# Sheet1.net
KiCad netlist of a schematic drawn in Altium Designer
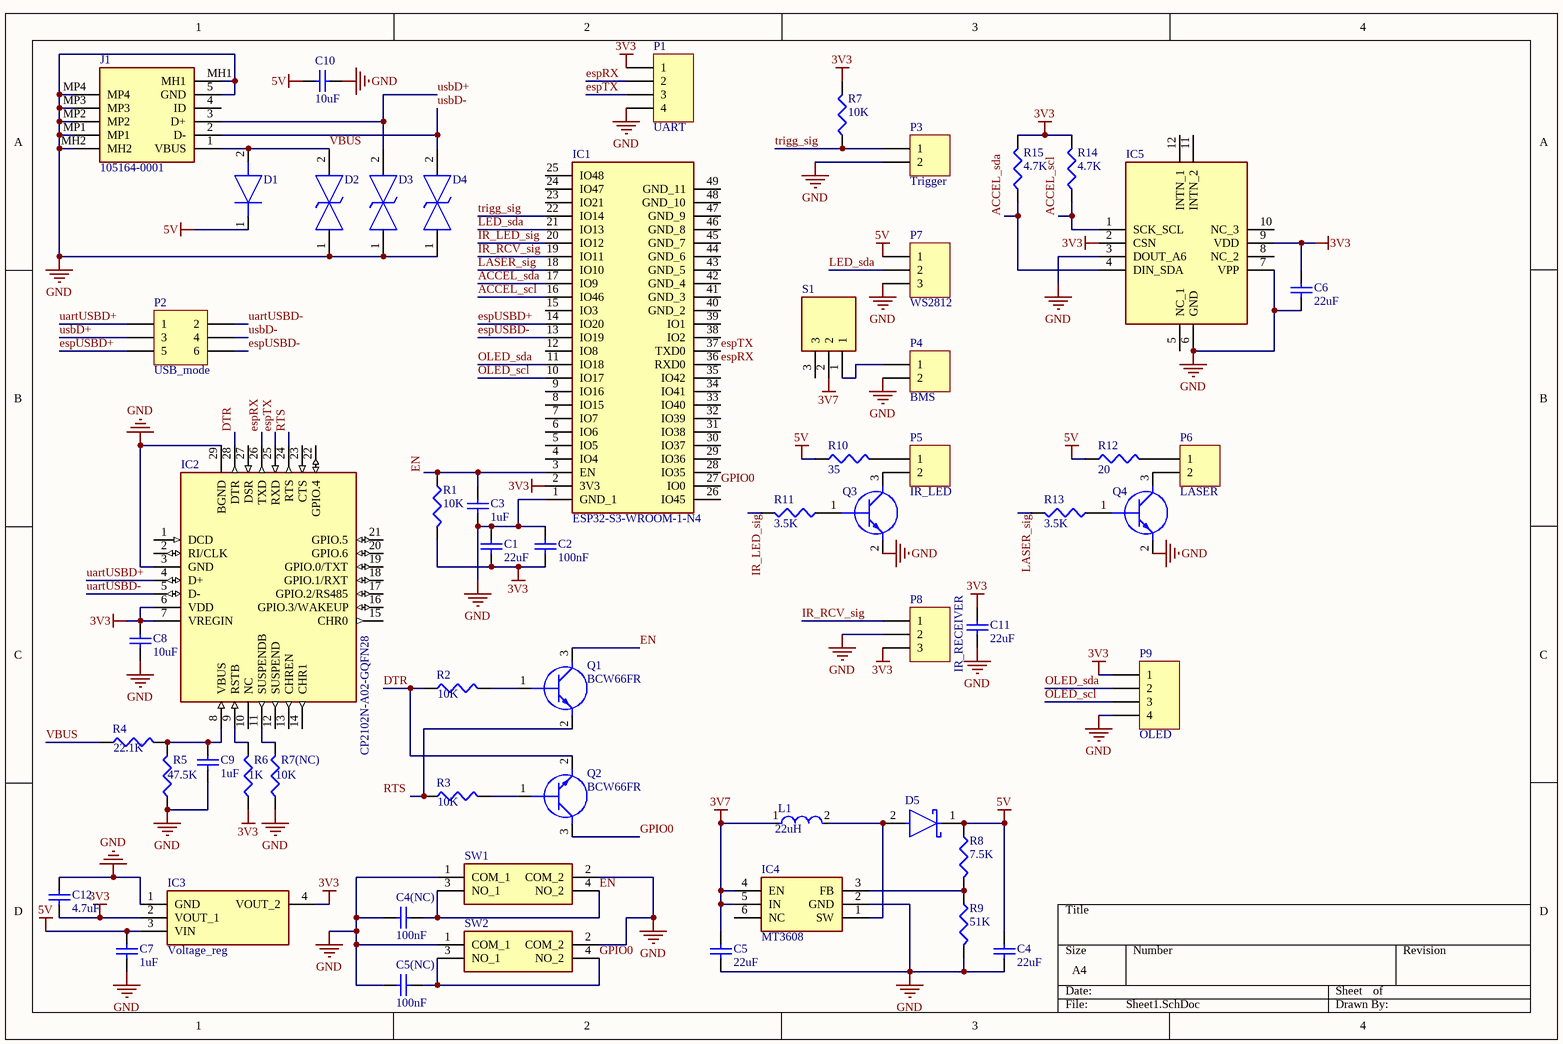
[diagram p0: Sheet1.SchDoc]

(export (version "E")
  (design (tool "Eeschema 10.0.6"))
  (components
    (comp (ref "C1")
      (value "22uF")
      (footprint "1608[0603]")
      (description "Capacitor (Semiconductor SIM Model)")
      (fields (field (name "Comment") "Cap Semi") (field (name "PUBLISHER") "Altium Limited"))
      (libsource (lib "Miscellaneous Devices") (part "Cap Semi"))
    )
    (comp (ref "C2")
      (value "100nF")
      (footprint "1608[0603]")
      (description "Capacitor (Semiconductor SIM Model)")
      (fields (field (name "Comment") "Cap Semi") (field (name "PUBLISHER") "Altium Limited"))
      (libsource (lib "Miscellaneous Devices") (part "Cap Semi"))
    )
    (comp (ref "C3")
      (value "1uF")
      (footprint "1608[0603]")
      (description "Capacitor (Semiconductor SIM Model)")
      (fields (field (name "Comment") "Cap Semi") (field (name "PUBLISHER") "Altium Limited"))
      (libsource (lib "Miscellaneous Devices") (part "Cap Semi"))
    )
    (comp (ref "C4")
      (value "22uF")
      (footprint "1608[0603]")
      (description "Capacitor (Semiconductor SIM Model)")
      (fields (field (name "Comment") "Cap Semi") (field (name "PUBLISHER") "Altium Limited"))
      (libsource (lib "Miscellaneous Devices") (part "Cap Semi"))
    )
    (comp (ref "C4(NC)")
      (value "100nF")
      (footprint "1608[0603]")
      (description "Capacitor (Semiconductor SIM Model)")
      (fields (field (name "Comment") "Cap Semi") (field (name "PUBLISHER") "Altium Limited"))
      (libsource (lib "Miscellaneous Devices") (part "Cap Semi"))
    )
    (comp (ref "C5")
      (value "22uF")
      (footprint "1608[0603]")
      (description "Capacitor (Semiconductor SIM Model)")
      (fields (field (name "Comment") "Cap Semi") (field (name "PUBLISHER") "Altium Limited"))
      (libsource (lib "Miscellaneous Devices") (part "Cap Semi"))
    )
    (comp (ref "C5(NC)")
      (value "100nF")
      (footprint "1608[0603]")
      (description "Capacitor (Semiconductor SIM Model)")
      (fields (field (name "Comment") "Cap Semi") (field (name "PUBLISHER") "Altium Limited"))
      (libsource (lib "Miscellaneous Devices") (part "Cap Semi"))
    )
    (comp (ref "C6")
      (value "22uF")
      (footprint "1608[0603]")
      (description "Capacitor (Semiconductor SIM Model)")
      (fields (field (name "Comment") "Cap Semi") (field (name "PUBLISHER") "Altium Limited"))
      (libsource (lib "Miscellaneous Devices") (part "Cap Semi"))
    )
    (comp (ref "C7")
      (value "1uF")
      (footprint "1608[0603]")
      (description "Capacitor (Semiconductor SIM Model)")
      (fields (field (name "Comment") "Cap Semi") (field (name "PUBLISHER") "Altium Limited"))
      (libsource (lib "Miscellaneous Devices") (part "Cap Semi"))
    )
    (comp (ref "C8")
      (value "10uF")
      (footprint "1608[0603]")
      (description "Capacitor (Semiconductor SIM Model)")
      (fields (field (name "Comment") "Cap Semi") (field (name "PUBLISHER") "Altium Limited"))
      (libsource (lib "Miscellaneous Devices") (part "Cap Semi"))
    )
    (comp (ref "C9")
      (value "1uF")
      (footprint "1608[0603]")
      (description "Capacitor (Semiconductor SIM Model)")
      (fields (field (name "Comment") "Cap Semi") (field (name "PUBLISHER") "Altium Limited"))
      (libsource (lib "Miscellaneous Devices") (part "Cap Semi"))
    )
    (comp (ref "C10")
      (value "10uF")
      (footprint "1608[0603]")
      (description "Capacitor (Semiconductor SIM Model)")
      (fields (field (name "Comment") "Cap Semi") (field (name "PUBLISHER") "Altium Limited"))
      (libsource (lib "Miscellaneous Devices") (part "Cap Semi"))
    )
    (comp (ref "C11")
      (value "22uF")
      (footprint "1608[0603]")
      (description "Capacitor (Semiconductor SIM Model)")
      (fields (field (name "Comment") "Cap Semi") (field (name "PUBLISHER") "Altium Limited"))
      (libsource (lib "Miscellaneous Devices") (part "Cap Semi"))
    )
    (comp (ref "C12")
      (value "4.7uF")
      (footprint "1608[0603]")
      (description "Capacitor (Semiconductor SIM Model)")
      (fields (field (name "Comment") "Cap Semi") (field (name "PUBLISHER") "Altium Limited"))
      (libsource (lib "Miscellaneous Devices") (part "Cap Semi"))
    )
    (comp (ref "D1")
      (value "1N5819HW-7-F")
      (footprint "SamacSys:SOD3716X145N")
      (description "Diode")
      (fields (field (name "MOUSER PART NUMBER") "621-1N5819HW-F"))
      (libsource (lib "*") (part "1N5819HW-7-F"))
    )
    (comp (ref "D2")
      (value "DF2B6M4CT,L3F")
      (footprint "SamacSys:DF2B6M4CTL3F")
      (description "TVS Diode (Bi-directional)")
      (fields (field (name "MOUSER PART NUMBER") "757-DF2B6M4CTL3F"))
      (libsource (lib "*") (part "DF2B6M4CT,L3F"))
    )
    (comp (ref "D3")
      (value "DF2B6M4CT,L3F")
      (footprint "SamacSys:DF2B6M4CTL3F")
      (description "TVS Diode (Bi-directional)")
      (fields (field (name "MOUSER PART NUMBER") "757-DF2B6M4CTL3F"))
      (libsource (lib "*") (part "DF2B6M4CT,L3F"))
    )
    (comp (ref "D4")
      (value "DF2B6M4CT,L3F")
      (footprint "SamacSys:DF2B6M4CTL3F")
      (description "TVS Diode (Bi-directional)")
      (fields (field (name "MOUSER PART NUMBER") "757-DF2B6M4CTL3F"))
      (libsource (lib "*") (part "DF2B6M4CT,L3F"))
    )
    (comp (ref "D5")
      (value "B340-13-F")
      (footprint "FP-SMC-MFG")
      (description "DIODE SCHOTTKY 40V 3A SMC")
      (fields
        (field (name "MANUFACTURER") "Diodes Inc.")
        (field (name "OCTOPART") "https://octopart.com/b340-13-f-diodes+inc.-325814")
      )
      (libsource (lib "Altium Content Vault") (part "1d6ec82d83fb6aee721767c19dac4b9"))
    )
    (comp (ref "IC1")
      (value "ESP32-S3-WROOM-1-N4")
      (footprint "SamacSys:ESP32S3WROOM1N4")
      (description "Integrated Circuit")
      (fields (field (name "MOUSER PART NUMBER") "356-ESP32-S3WROOM1N4"))
      (libsource (lib "*") (part "ESP32-S3-WROOM-1-N4"))
    )
    (comp (ref "IC2")
      (value "CP2102N-A02-GQFN28")
      (footprint "SamacSys:QFN50P500X500X80-29N-D")
      (description "Integrated Circuit")
      (fields (field (name "MOUSER PART NUMBER") "634-CP2102NA02GQFN28"))
      (libsource (lib "*") (part "CP2102N-A02-GQFN28"))
    )
    (comp (ref "IC3")
      (value "Voltage_reg")
      (footprint "SamacSys:SOT230P700X180-4N")
      (description "Integrated Circuit")
      (fields
        (field (name "MANUFACTURER_PART_NUMBER") "LDL1117S33R")
        (field (name "MOUSER PART NUMBER") "511-LDL1117S33R")
      )
      (libsource (lib "*") (part "LDL1117S33R"))
    )
    (comp (ref "IC4")
      (value "MT3608")
      (footprint "SamacSys:SOT95P280X145-6N")
      (description "Integrated Circuit")
      (libsource (lib "*") (part "MT3608"))
    )
    (comp (ref "IC5")
      (value "MC3479")
      (footprint "SamacSys:MC3479")
      (description "Integrated Circuit")
      (fields (field (name "MOUSER PART NUMBER") "498-MC3479"))
      (libsource (lib "*") (part "MC3479"))
    )
    (comp (ref "J1")
      (value "105164-0001")
      (footprint "SamacSys:1051640001")
      (description "Connector")
      (fields (field (name "MOUSER PART NUMBER") "538-105164-0001"))
      (libsource (lib "*") (part "105164-0001"))
    )
    (comp (ref "L1")
      (value "22uH")
      (footprint "FP-SRN8040-MFG")
      (description "FIXED IND 22UH 2.2A 100 MOHM SMD")
      (fields (field (name "TOLERANCE") "20%") (field (name "Comment") "SRN8040-220M"))
      (libsource (lib "Altium Content Vault") (part "725321dda6339637d4d059423bc1c3c"))
    )
    (comp (ref "P1")
      (value "UART")
      (footprint "HDR1X4")
      (description "Header, 4-Pin")
      (fields (field (name "PUBLISHER") "Altium Limited"))
      (libsource (lib "Miscellaneous Connectors") (part "Header 4"))
    )
    (comp (ref "P2")
      (value "USB_mode")
      (footprint "HDR2X3")
      (description "Header, 3-Pin, Dual row")
      (fields (field (name "PUBLISHER") "Altium Limited"))
      (libsource (lib "Miscellaneous Connectors") (part "Header 3X2"))
    )
    (comp (ref "P3")
      (value "Trigger")
      (footprint "HDR1X2")
      (description "Header, 2-Pin")
      (fields (field (name "PUBLISHER") "Altium Limited"))
      (libsource (lib "Miscellaneous Connectors") (part "Header 2"))
    )
    (comp (ref "P4")
      (value "BMS")
      (footprint "HDR1X2")
      (description "Header, 2-Pin")
      (fields (field (name "PUBLISHER") "Altium Limited"))
      (libsource (lib "Miscellaneous Connectors") (part "Header 2"))
    )
    (comp (ref "P5")
      (value "IR_LED")
      (footprint "HDR1X2")
      (description "Header, 2-Pin")
      (fields (field (name "PUBLISHER") "Altium Limited"))
      (libsource (lib "Miscellaneous Connectors") (part "Header 2"))
    )
    (comp (ref "P6")
      (value "LASER")
      (footprint "HDR1X2")
      (description "Header, 2-Pin")
      (fields (field (name "PUBLISHER") "Altium Limited"))
      (libsource (lib "Miscellaneous Connectors") (part "Header 2"))
    )
    (comp (ref "P7")
      (value "WS2812")
      (footprint "HDR1X3")
      (description "Header, 3-Pin")
      (fields (field (name "PUBLISHER") "Altium Limited"))
      (libsource (lib "Miscellaneous Connectors") (part "Header 3"))
    )
    (comp (ref "P8")
      (value "IR_RECEIVER")
      (footprint "HDR1X3")
      (description "Header, 3-Pin")
      (fields (field (name "PUBLISHER") "Altium Limited"))
      (libsource (lib "Miscellaneous Connectors") (part "Header 3"))
    )
    (comp (ref "P9")
      (value "OLED")
      (footprint "HDR1X4")
      (description "Header, 4-Pin")
      (fields (field (name "PUBLISHER") "Altium Limited"))
      (libsource (lib "Miscellaneous Connectors") (part "Header 4"))
    )
    (comp (ref "Q1")
      (value "BCW66FR")
      (footprint "SamacSys:SOT95P230X110-3N")
      (description "Transistor BJT NPN")
      (fields (field (name "MOUSER PART NUMBER") "771-BCW66FR"))
      (libsource (lib "*") (part "BCW66FR"))
    )
    (comp (ref "Q2")
      (value "BCW66FR")
      (footprint "SamacSys:SOT95P230X110-3N")
      (description "Transistor BJT NPN")
      (fields (field (name "MOUSER PART NUMBER") "771-BCW66FR"))
      (libsource (lib "*") (part "BCW66FR"))
    )
    (comp (ref "Q3")
      (value "BCW66FR")
      (footprint "SamacSys:SOT95P230X110-3N")
      (description "Transistor BJT NPN")
      (fields (field (name "MOUSER PART NUMBER") "771-BCW66FR"))
      (libsource (lib "*") (part "BCW66FR"))
    )
    (comp (ref "Q4")
      (value "BCW66FR")
      (footprint "SamacSys:SOT95P230X110-3N")
      (description "Transistor BJT NPN")
      (fields (field (name "MOUSER PART NUMBER") "771-BCW66FR"))
      (libsource (lib "*") (part "BCW66FR"))
    )
    (comp (ref "R1")
      (value "10K")
      (footprint "J1-0603")
      (description "Resistor")
      (fields (field (name "Comment") "Res3") (field (name "PUBLISHER") "Altium Limited"))
      (libsource (lib "Miscellaneous Devices") (part "Res3"))
    )
    (comp (ref "R2")
      (value "10K")
      (footprint "J1-0603")
      (description "Resistor")
      (fields (field (name "Comment") "Res3") (field (name "PUBLISHER") "Altium Limited"))
      (libsource (lib "Miscellaneous Devices") (part "Res3"))
    )
    (comp (ref "R3")
      (value "10K")
      (footprint "J1-0603")
      (description "Resistor")
      (fields (field (name "Comment") "Res3") (field (name "PUBLISHER") "Altium Limited"))
      (libsource (lib "Miscellaneous Devices") (part "Res3"))
    )
    (comp (ref "R4")
      (value "22.1K")
      (footprint "J1-0603")
      (description "Resistor")
      (fields (field (name "Comment") "Res3") (field (name "PUBLISHER") "Altium Limited"))
      (libsource (lib "Miscellaneous Devices") (part "Res3"))
    )
    (comp (ref "R5")
      (value "47.5K")
      (footprint "J1-0603")
      (description "Resistor")
      (fields (field (name "Comment") "Res3") (field (name "PUBLISHER") "Altium Limited"))
      (libsource (lib "Miscellaneous Devices") (part "Res3"))
    )
    (comp (ref "R6")
      (value "1K")
      (footprint "J1-0603")
      (description "Resistor")
      (fields (field (name "Comment") "Res3") (field (name "PUBLISHER") "Altium Limited"))
      (libsource (lib "Miscellaneous Devices") (part "Res3"))
    )
    (comp (ref "R7")
      (value "10K")
      (footprint "J1-0603")
      (description "Resistor")
      (fields (field (name "Comment") "Res3") (field (name "PUBLISHER") "Altium Limited"))
      (libsource (lib "Miscellaneous Devices") (part "Res3"))
    )
    (comp (ref "R7(NC)")
      (value "10K")
      (footprint "J1-0603")
      (description "Resistor")
      (fields (field (name "Comment") "Res3") (field (name "PUBLISHER") "Altium Limited"))
      (libsource (lib "Miscellaneous Devices") (part "Res3"))
    )
    (comp (ref "R8")
      (value "7.5K")
      (footprint "J1-0603")
      (description "Resistor")
      (fields (field (name "Comment") "Res3") (field (name "PUBLISHER") "Altium Limited"))
      (libsource (lib "Miscellaneous Devices") (part "Res3"))
    )
    (comp (ref "R9")
      (value "51K")
      (footprint "J1-0603")
      (description "Resistor")
      (fields (field (name "Comment") "Res3") (field (name "PUBLISHER") "Altium Limited"))
      (libsource (lib "Miscellaneous Devices") (part "Res3"))
    )
    (comp (ref "R10")
      (value "35")
      (footprint "J1-0603")
      (description "Resistor")
      (fields (field (name "Comment") "Res3") (field (name "PUBLISHER") "Altium Limited"))
      (libsource (lib "Miscellaneous Devices") (part "Res3"))
    )
    (comp (ref "R11")
      (value "3.5K")
      (footprint "J1-0603")
      (description "Resistor")
      (fields (field (name "Comment") "Res3") (field (name "PUBLISHER") "Altium Limited"))
      (libsource (lib "Miscellaneous Devices") (part "Res3"))
    )
    (comp (ref "R12")
      (value "20")
      (footprint "J1-0603")
      (description "Resistor")
      (fields (field (name "Comment") "Res3") (field (name "PUBLISHER") "Altium Limited"))
      (libsource (lib "Miscellaneous Devices") (part "Res3"))
    )
    (comp (ref "R13")
      (value "3.5K")
      (footprint "J1-0603")
      (description "Resistor")
      (fields (field (name "Comment") "Res3") (field (name "PUBLISHER") "Altium Limited"))
      (libsource (lib "Miscellaneous Devices") (part "Res3"))
    )
    (comp (ref "R14")
      (value "4.7K")
      (footprint "J1-0603")
      (description "Resistor")
      (fields (field (name "Comment") "Res3") (field (name "PUBLISHER") "Altium Limited"))
      (libsource (lib "Miscellaneous Devices") (part "Res3"))
    )
    (comp (ref "R15")
      (value "4.7K")
      (footprint "J1-0603")
      (description "Resistor")
      (fields (field (name "Comment") "Res3") (field (name "PUBLISHER") "Altium Limited"))
      (libsource (lib "Miscellaneous Devices") (part "Res3"))
    )
    (comp (ref "S1")
      (value "1101M2S3CQE2")
      (footprint "SamacSys:1000-SERIES(SPDT)")
      (description "Switch")
      (fields (field (name "MOUSER PART NUMBER") "611-1101M2S3CQE2"))
      (libsource (lib "*") (part "1101M2S3CQE2"))
    )
    (comp (ref "SW1")
      (value "PTS526_SM15_SMTR2_LFS")
      (footprint "SamacSys:PTS526SM15SMTR2LFS")
      (description "Switch")
      (fields
        (field (name "MANUFACTURER_PART_NUMBER") "PTS526 SM15 SMTR2 LFS")
        (field (name "MOUSER PART NUMBER") "611-PTS526SM15SMTR2L")
      )
      (libsource (lib "SamacSys") (part "PTS526_SM15_SMTR2_LFS"))
    )
    (comp (ref "SW2")
      (value "PTS526_SM15_SMTR2_LFS")
      (footprint "SamacSys:PTS526SM15SMTR2LFS")
      (description "Switch")
      (fields
        (field (name "MANUFACTURER_PART_NUMBER") "PTS526 SM15 SMTR2 LFS")
        (field (name "MOUSER PART NUMBER") "611-PTS526SM15SMTR2L")
      )
      (libsource (lib "SamacSys") (part "PTS526_SM15_SMTR2_LFS"))
    )
  )
  (nets
    (net (code "1") (name "/ACCEL_scl") (class "Default")
      (node (ref "IC1") (pin "16") (pinfunction "IO46_16") (pintype "passive"))
      (node (ref "IC5") (pin "1") (pinfunction "SCK_SCL_1") (pintype "passive"))
      (node (ref "R14") (pin "1") (pinfunction "1_1") (pintype "passive"))
    )
    (net (code "2") (name "/ACCEL_sda") (class "Default")
      (node (ref "IC1") (pin "17") (pinfunction "IO9_17") (pintype "passive"))
      (node (ref "IC5") (pin "4") (pinfunction "DIN_SDA_4") (pintype "passive"))
      (node (ref "R15") (pin "1") (pinfunction "1_1") (pintype "passive"))
    )
    (net (code "3") (name "/DTR") (class "Default")
      (node (ref "IC2") (pin "28") (pinfunction "DTR_28") (pintype "output"))
      (node (ref "Q2") (pin "2") (pinfunction "E_2") (pintype "passive"))
      (node (ref "R2") (pin "1") (pinfunction "1_1") (pintype "passive"))
    )
    (net (code "4") (name "/EN") (class "Default")
      (node (ref "C3") (pin "1") (pinfunction "1_1") (pintype "passive"))
      (node (ref "C4(NC)") (pin "1") (pinfunction "1_1") (pintype "passive"))
      (node (ref "IC1") (pin "3") (pinfunction "EN_3") (pintype "passive"))
      (node (ref "Q1") (pin "3") (pinfunction "C_3") (pintype "passive"))
      (node (ref "R1") (pin "2") (pinfunction "2_2") (pintype "passive"))
      (node (ref "SW1") (pin "3") (pinfunction "NO_1_3") (pintype "passive"))
      (node (ref "SW1") (pin "4") (pinfunction "NO_2_4") (pintype "passive"))
    )
    (net (code "5") (name "/GPIO0") (class "Default")
      (node (ref "C5(NC)") (pin "1") (pinfunction "1_1") (pintype "passive"))
      (node (ref "IC1") (pin "27") (pinfunction "IO0_27") (pintype "passive"))
      (node (ref "Q2") (pin "3") (pinfunction "C_3") (pintype "passive"))
      (node (ref "SW2") (pin "3") (pinfunction "NO_1_3") (pintype "passive"))
      (node (ref "SW2") (pin "4") (pinfunction "NO_2_4") (pintype "passive"))
    )
    (net (code "6") (name "/IR_LED_sig") (class "Default")
      (node (ref "IC1") (pin "20") (pinfunction "IO12_20") (pintype "passive"))
      (node (ref "R11") (pin "2") (pinfunction "2_2") (pintype "passive"))
    )
    (net (code "7") (name "/IR_RCV_sig") (class "Default")
      (node (ref "IC1") (pin "19") (pinfunction "IO11_19") (pintype "passive"))
      (node (ref "P8") (pin "1") (pinfunction "1_1") (pintype "passive"))
    )
    (net (code "8") (name "/LASER_sig") (class "Default")
      (node (ref "IC1") (pin "18") (pinfunction "IO10_18") (pintype "passive"))
      (node (ref "R13") (pin "2") (pinfunction "2_2") (pintype "passive"))
    )
    (net (code "9") (name "/LED_sda") (class "Default")
      (node (ref "IC1") (pin "21") (pinfunction "IO13_21") (pintype "passive"))
      (node (ref "P7") (pin "2") (pinfunction "2_2") (pintype "passive"))
    )
    (net (code "10") (name "/OLED_scl") (class "Default")
      (node (ref "IC1") (pin "10") (pinfunction "IO17_10") (pintype "passive"))
      (node (ref "P9") (pin "3") (pinfunction "3_3") (pintype "passive"))
    )
    (net (code "11") (name "/OLED_sda") (class "Default")
      (node (ref "IC1") (pin "11") (pinfunction "IO18_11") (pintype "passive"))
      (node (ref "P9") (pin "2") (pinfunction "2_2") (pintype "passive"))
    )
    (net (code "12") (name "/RTS") (class "Default")
      (node (ref "IC2") (pin "24") (pinfunction "RTS_24") (pintype "output"))
    )
    (net (code "13") (name "/VBUS") (class "Default")
      (node (ref "D1") (pin "2") (pinfunction "A_2") (pintype "passive"))
      (node (ref "D2") (pin "2") (pinfunction "2_2") (pintype "passive"))
      (node (ref "J1") (pin "1") (pinfunction "VBUS_1") (pintype "passive"))
      (node (ref "R4") (pin "1") (pinfunction "1_1") (pintype "passive"))
    )
    (net (code "14") (name "/espRX") (class "Default")
      (node (ref "IC1") (pin "36") (pinfunction "RXD0_36") (pintype "passive"))
      (node (ref "IC2") (pin "26") (pinfunction "TXD_26") (pintype "output"))
      (node (ref "P1") (pin "2") (pinfunction "2_2") (pintype "passive"))
    )
    (net (code "15") (name "/espTX") (class "Default")
      (node (ref "IC1") (pin "37") (pinfunction "TXD0_37") (pintype "passive"))
      (node (ref "IC2") (pin "25") (pinfunction "RXD_25") (pintype "input"))
      (node (ref "P1") (pin "3") (pinfunction "3_3") (pintype "passive"))
    )
    (net (code "16") (name "/espUSBD+") (class "Default")
      (node (ref "IC1") (pin "14") (pinfunction "IO20_14") (pintype "passive"))
      (node (ref "P2") (pin "5") (pinfunction "5_5") (pintype "passive"))
    )
    (net (code "17") (name "/espUSBD-") (class "Default")
      (node (ref "IC1") (pin "13") (pinfunction "IO19_13") (pintype "passive"))
      (node (ref "P2") (pin "6") (pinfunction "6_6") (pintype "passive"))
    )
    (net (code "18") (name "/trigg_sig") (class "Default")
      (node (ref "IC1") (pin "22") (pinfunction "IO14_22") (pintype "passive"))
      (node (ref "P3") (pin "1") (pinfunction "1_1") (pintype "passive"))
      (node (ref "R7") (pin "1") (pinfunction "1_1") (pintype "passive"))
    )
    (net (code "19") (name "/uartUSBD+") (class "Default")
      (node (ref "IC2") (pin "4") (pinfunction "D+_4") (pintype "bidirectional"))
      (node (ref "P2") (pin "1") (pinfunction "1_1") (pintype "passive"))
    )
    (net (code "20") (name "/uartUSBD-") (class "Default")
      (node (ref "IC2") (pin "5") (pinfunction "D-_5") (pintype "bidirectional"))
      (node (ref "P2") (pin "2") (pinfunction "2_2") (pintype "passive"))
    )
    (net (code "21") (name "/usbD+") (class "Default")
      (node (ref "D3") (pin "2") (pinfunction "2_2") (pintype "passive"))
      (node (ref "J1") (pin "3") (pinfunction "D+_3") (pintype "passive"))
      (node (ref "P2") (pin "3") (pinfunction "3_3") (pintype "passive"))
    )
    (net (code "22") (name "/usbD-") (class "Default")
      (node (ref "D4") (pin "2") (pinfunction "2_2") (pintype "passive"))
      (node (ref "J1") (pin "2") (pinfunction "D-_2") (pintype "passive"))
      (node (ref "P2") (pin "4") (pinfunction "4_4") (pintype "passive"))
    )
    (net (code "23") (name "3V3") (class "Default")
      (node (ref "C1") (pin "2") (pinfunction "2_2") (pintype "passive"))
      (node (ref "C11") (pin "1") (pinfunction "1_1") (pintype "passive"))
      (node (ref "C12") (pin "2") (pinfunction "2_2") (pintype "passive"))
      (node (ref "C2") (pin "2") (pinfunction "2_2") (pintype "passive"))
      (node (ref "C6") (pin "1") (pinfunction "1_1") (pintype "passive"))
      (node (ref "C8") (pin "2") (pinfunction "2_2") (pintype "passive"))
      (node (ref "IC1") (pin "2") (pinfunction "3V3_2") (pintype "passive"))
      (node (ref "IC2") (pin "6") (pinfunction "VDD_6") (pintype "power_in"))
      (node (ref "IC2") (pin "7") (pinfunction "VREGIN_7") (pintype "power_in"))
      (node (ref "IC3") (pin "2") (pinfunction "VOUT_1_2") (pintype "power_in"))
      (node (ref "IC3") (pin "4") (pinfunction "VOUT_2_4") (pintype "power_in"))
      (node (ref "IC5") (pin "2") (pinfunction "CSN_2") (pintype "passive"))
      (node (ref "IC5") (pin "9") (pinfunction "VDD_9") (pintype "passive"))
      (node (ref "P1") (pin "1") (pinfunction "1_1") (pintype "passive"))
      (node (ref "P8") (pin "3") (pinfunction "3_3") (pintype "passive"))
      (node (ref "P9") (pin "1") (pinfunction "1_1") (pintype "passive"))
      (node (ref "R1") (pin "1") (pinfunction "1_1") (pintype "passive"))
      (node (ref "R14") (pin "2") (pinfunction "2_2") (pintype "passive"))
      (node (ref "R15") (pin "2") (pinfunction "2_2") (pintype "passive"))
      (node (ref "R6") (pin "1") (pinfunction "1_1") (pintype "passive"))
      (node (ref "R7") (pin "2") (pinfunction "2_2") (pintype "passive"))
    )
    (net (code "24") (name "3V7") (class "Default")
      (node (ref "C5") (pin "1") (pinfunction "1_1") (pintype "passive"))
      (node (ref "IC4") (pin "4") (pinfunction "EN_4") (pintype "passive"))
      (node (ref "IC4") (pin "5") (pinfunction "IN_5") (pintype "passive"))
      (node (ref "L1") (pin "1") (pinfunction "1_1") (pintype "passive"))
      (node (ref "S1") (pin "2") (pinfunction "2_2") (pintype "passive"))
    )
    (net (code "25") (name "5V") (class "Default")
      (node (ref "C10") (pin "2") (pinfunction "2_2") (pintype "passive"))
      (node (ref "C4") (pin "1") (pinfunction "1_1") (pintype "passive"))
      (node (ref "C7") (pin "1") (pinfunction "1_1") (pintype "passive"))
      (node (ref "D1") (pin "1") (pinfunction "K_1") (pintype "passive"))
      (node (ref "D5") (pin "1") (pinfunction "C_1") (pintype "passive"))
      (node (ref "IC3") (pin "3") (pinfunction "VIN_3") (pintype "power_in"))
      (node (ref "P7") (pin "1") (pinfunction "1_1") (pintype "passive"))
      (node (ref "R10") (pin "1") (pinfunction "1_1") (pintype "passive"))
      (node (ref "R12") (pin "1") (pinfunction "1_1") (pintype "passive"))
      (node (ref "R8") (pin "2") (pinfunction "2_2") (pintype "passive"))
    )
    (net (code "26") (name "GND") (class "Default")
      (node (ref "C1") (pin "1") (pinfunction "1_1") (pintype "passive"))
      (node (ref "C10") (pin "1") (pinfunction "1_1") (pintype "passive"))
      (node (ref "C11") (pin "2") (pinfunction "2_2") (pintype "passive"))
      (node (ref "C12") (pin "1") (pinfunction "1_1") (pintype "passive"))
      (node (ref "C2") (pin "1") (pinfunction "1_1") (pintype "passive"))
      (node (ref "C3") (pin "2") (pinfunction "2_2") (pintype "passive"))
      (node (ref "C4") (pin "2") (pinfunction "2_2") (pintype "passive"))
      (node (ref "C4(NC)") (pin "2") (pinfunction "2_2") (pintype "passive"))
      (node (ref "C5") (pin "2") (pinfunction "2_2") (pintype "passive"))
      (node (ref "C5(NC)") (pin "2") (pinfunction "2_2") (pintype "passive"))
      (node (ref "C6") (pin "2") (pinfunction "2_2") (pintype "passive"))
      (node (ref "C7") (pin "2") (pinfunction "2_2") (pintype "passive"))
      (node (ref "C8") (pin "1") (pinfunction "1_1") (pintype "passive"))
      (node (ref "C9") (pin "1") (pinfunction "1_1") (pintype "passive"))
      (node (ref "D2") (pin "1") (pinfunction "1_1") (pintype "passive"))
      (node (ref "D3") (pin "1") (pinfunction "1_1") (pintype "passive"))
      (node (ref "D4") (pin "1") (pinfunction "1_1") (pintype "passive"))
      (node (ref "IC1") (pin "1") (pinfunction "GND_1_1") (pintype "passive"))
      (node (ref "IC2") (pin "29") (pinfunction "BGND_29") (pintype "power_in"))
      (node (ref "IC2") (pin "3") (pinfunction "GND_3") (pintype "power_in"))
      (node (ref "IC3") (pin "1") (pinfunction "GND_1") (pintype "power_in"))
      (node (ref "IC4") (pin "2") (pinfunction "GND_2") (pintype "passive"))
      (node (ref "IC5") (pin "3") (pinfunction "DOUT_A6_3") (pintype "passive"))
      (node (ref "IC5") (pin "6") (pinfunction "GND_6") (pintype "passive"))
      (node (ref "IC5") (pin "7") (pinfunction "VPP_7") (pintype "passive"))
      (node (ref "J1") (pin "5") (pinfunction "GND_5") (pintype "passive"))
      (node (ref "J1") (pin "MH1") (pinfunction "MH1_MH1") (pintype "passive"))
      (node (ref "J1") (pin "MH2") (pinfunction "MH2_MH2") (pintype "passive"))
      (node (ref "J1") (pin "MP1") (pinfunction "MP1_MP1") (pintype "passive"))
      (node (ref "J1") (pin "MP2") (pinfunction "MP2_MP2") (pintype "passive"))
      (node (ref "J1") (pin "MP3") (pinfunction "MP3_MP3") (pintype "passive"))
      (node (ref "J1") (pin "MP4") (pinfunction "MP4_MP4") (pintype "passive"))
      (node (ref "P1") (pin "4") (pinfunction "4_4") (pintype "passive"))
      (node (ref "P3") (pin "2") (pinfunction "2_2") (pintype "passive"))
      (node (ref "P4") (pin "2") (pinfunction "2_2") (pintype "passive"))
      (node (ref "P7") (pin "3") (pinfunction "3_3") (pintype "passive"))
      (node (ref "P8") (pin "2") (pinfunction "2_2") (pintype "passive"))
      (node (ref "P9") (pin "4") (pinfunction "4_4") (pintype "passive"))
      (node (ref "Q3") (pin "2") (pinfunction "E_2") (pintype "passive"))
      (node (ref "Q4") (pin "2") (pinfunction "E_2") (pintype "passive"))
      (node (ref "R5") (pin "1") (pinfunction "1_1") (pintype "passive"))
      (node (ref "R7(NC)") (pin "1") (pinfunction "1_1") (pintype "passive"))
      (node (ref "R9") (pin "1") (pinfunction "1_1") (pintype "passive"))
      (node (ref "SW1") (pin "1") (pinfunction "COM_1_1") (pintype "passive"))
      (node (ref "SW1") (pin "2") (pinfunction "COM_2_2") (pintype "passive"))
      (node (ref "SW2") (pin "1") (pinfunction "COM_1_1") (pintype "passive"))
      (node (ref "SW2") (pin "2") (pinfunction "COM_2_2") (pintype "passive"))
    )
    (net (code "27") (name "Net-(D5-A)") (class "Default")
      (node (ref "D5") (pin "2") (pinfunction "A_2") (pintype "passive"))
      (node (ref "IC4") (pin "1") (pinfunction "SW_1") (pintype "passive"))
      (node (ref "L1") (pin "2") (pinfunction "2_2") (pintype "passive"))
    )
    (net (code "28") (name "Net-(IC2-RSTB)") (class "Default")
      (node (ref "IC2") (pin "9") (pinfunction "RSTB_9") (pintype "input"))
      (node (ref "R6") (pin "2") (pinfunction "2_2") (pintype "passive"))
    )
    (net (code "29") (name "Net-(IC2-SUSPENDB)") (class "Default")
      (node (ref "IC2") (pin "11") (pinfunction "SUSPENDB_11") (pintype "output"))
      (node (ref "R7(NC)") (pin "2") (pinfunction "2_2") (pintype "passive"))
    )
    (net (code "30") (name "Net-(IC2-VBUS)") (class "Default")
      (node (ref "C9") (pin "2") (pinfunction "2_2") (pintype "passive"))
      (node (ref "IC2") (pin "8") (pinfunction "VBUS_8") (pintype "input"))
      (node (ref "R4") (pin "2") (pinfunction "2_2") (pintype "passive"))
      (node (ref "R5") (pin "2") (pinfunction "2_2") (pintype "passive"))
    )
    (net (code "31") (name "Net-(IC4-FB)") (class "Default")
      (node (ref "IC4") (pin "3") (pinfunction "FB_3") (pintype "passive"))
      (node (ref "R8") (pin "1") (pinfunction "1_1") (pintype "passive"))
      (node (ref "R9") (pin "2") (pinfunction "2_2") (pintype "passive"))
    )
    (net (code "32") (name "Net-(P4-Pad1)") (class "Default")
      (node (ref "P4") (pin "1") (pinfunction "1_1") (pintype "passive"))
      (node (ref "S1") (pin "1") (pinfunction "1_1") (pintype "passive"))
    )
    (net (code "33") (name "Net-(P5-Pad1)") (class "Default")
      (node (ref "P5") (pin "1") (pinfunction "1_1") (pintype "passive"))
      (node (ref "R10") (pin "2") (pinfunction "2_2") (pintype "passive"))
    )
    (net (code "34") (name "Net-(P6-Pad1)") (class "Default")
      (node (ref "P6") (pin "1") (pinfunction "1_1") (pintype "passive"))
      (node (ref "R12") (pin "2") (pinfunction "2_2") (pintype "passive"))
    )
    (net (code "35") (name "Net-(Q1-B)") (class "Default")
      (node (ref "Q1") (pin "1") (pinfunction "B_1") (pintype "passive"))
      (node (ref "R2") (pin "2") (pinfunction "2_2") (pintype "passive"))
    )
    (net (code "36") (name "Net-(Q1-E)") (class "Default")
      (node (ref "Q1") (pin "2") (pinfunction "E_2") (pintype "passive"))
      (node (ref "R3") (pin "1") (pinfunction "1_1") (pintype "passive"))
    )
    (net (code "37") (name "Net-(Q2-B)") (class "Default")
      (node (ref "Q2") (pin "1") (pinfunction "B_1") (pintype "passive"))
      (node (ref "R3") (pin "2") (pinfunction "2_2") (pintype "passive"))
    )
    (net (code "38") (name "Net-(Q3-B)") (class "Default")
      (node (ref "Q3") (pin "1") (pinfunction "B_1") (pintype "passive"))
      (node (ref "R11") (pin "1") (pinfunction "1_1") (pintype "passive"))
    )
    (net (code "39") (name "Net-(Q3-C)") (class "Default")
      (node (ref "P5") (pin "2") (pinfunction "2_2") (pintype "passive"))
      (node (ref "Q3") (pin "3") (pinfunction "C_3") (pintype "passive"))
    )
    (net (code "40") (name "Net-(Q4-B)") (class "Default")
      (node (ref "Q4") (pin "1") (pinfunction "B_1") (pintype "passive"))
      (node (ref "R13") (pin "1") (pinfunction "1_1") (pintype "passive"))
    )
    (net (code "41") (name "Net-(Q4-C)") (class "Default")
      (node (ref "P6") (pin "2") (pinfunction "2_2") (pintype "passive"))
      (node (ref "Q4") (pin "3") (pinfunction "C_3") (pintype "passive"))
    )
    (net (code "42") (name "unconnected-(IC1-GND_2-Pad40)") (class "Default")
      (node (ref "IC1") (pin "40") (pinfunction "GND_2_40") (pintype "passive"))
    )
    (net (code "43") (name "unconnected-(IC1-GND_3-Pad41)") (class "Default")
      (node (ref "IC1") (pin "41") (pinfunction "GND_3_41") (pintype "passive"))
    )
    (net (code "44") (name "unconnected-(IC1-GND_4-Pad42)") (class "Default")
      (node (ref "IC1") (pin "42") (pinfunction "GND_4_42") (pintype "passive"))
    )
    (net (code "45") (name "unconnected-(IC1-GND_5-Pad43)") (class "Default")
      (node (ref "IC1") (pin "43") (pinfunction "GND_5_43") (pintype "passive"))
    )
    (net (code "46") (name "unconnected-(IC1-GND_6-Pad44)") (class "Default")
      (node (ref "IC1") (pin "44") (pinfunction "GND_6_44") (pintype "passive"))
    )
    (net (code "47") (name "unconnected-(IC1-GND_7-Pad45)") (class "Default")
      (node (ref "IC1") (pin "45") (pinfunction "GND_7_45") (pintype "passive"))
    )
    (net (code "48") (name "unconnected-(IC1-GND_8-Pad46)") (class "Default")
      (node (ref "IC1") (pin "46") (pinfunction "GND_8_46") (pintype "passive"))
    )
    (net (code "49") (name "unconnected-(IC1-GND_9-Pad47)") (class "Default")
      (node (ref "IC1") (pin "47") (pinfunction "GND_9_47") (pintype "passive"))
    )
    (net (code "50") (name "unconnected-(IC1-GND_10-Pad48)") (class "Default")
      (node (ref "IC1") (pin "48") (pinfunction "GND_10_48") (pintype "passive"))
    )
    (net (code "51") (name "unconnected-(IC1-GND_11-Pad49)") (class "Default")
      (node (ref "IC1") (pin "49") (pinfunction "GND_11_49") (pintype "passive"))
    )
    (net (code "52") (name "unconnected-(IC1-IO1-Pad39)") (class "Default")
      (node (ref "IC1") (pin "39") (pinfunction "IO1_39") (pintype "passive"))
    )
    (net (code "53") (name "unconnected-(IC1-IO2-Pad38)") (class "Default")
      (node (ref "IC1") (pin "38") (pinfunction "IO2_38") (pintype "passive"))
    )
    (net (code "54") (name "unconnected-(IC1-IO3-Pad15)") (class "Default")
      (node (ref "IC1") (pin "15") (pinfunction "IO3_15") (pintype "passive"))
    )
    (net (code "55") (name "unconnected-(IC1-IO4-Pad4)") (class "Default")
      (node (ref "IC1") (pin "4") (pinfunction "IO4_4") (pintype "passive"))
    )
    (net (code "56") (name "unconnected-(IC1-IO5-Pad5)") (class "Default")
      (node (ref "IC1") (pin "5") (pinfunction "IO5_5") (pintype "passive"))
    )
    (net (code "57") (name "unconnected-(IC1-IO6-Pad6)") (class "Default")
      (node (ref "IC1") (pin "6") (pinfunction "IO6_6") (pintype "passive"))
    )
    (net (code "58") (name "unconnected-(IC1-IO7-Pad7)") (class "Default")
      (node (ref "IC1") (pin "7") (pinfunction "IO7_7") (pintype "passive"))
    )
    (net (code "59") (name "unconnected-(IC1-IO8-Pad12)") (class "Default")
      (node (ref "IC1") (pin "12") (pinfunction "IO8_12") (pintype "passive"))
    )
    (net (code "60") (name "unconnected-(IC1-IO15-Pad8)") (class "Default")
      (node (ref "IC1") (pin "8") (pinfunction "IO15_8") (pintype "passive"))
    )
    (net (code "61") (name "unconnected-(IC1-IO16-Pad9)") (class "Default")
      (node (ref "IC1") (pin "9") (pinfunction "IO16_9") (pintype "passive"))
    )
    (net (code "62") (name "unconnected-(IC1-IO21-Pad23)") (class "Default")
      (node (ref "IC1") (pin "23") (pinfunction "IO21_23") (pintype "passive"))
    )
    (net (code "63") (name "unconnected-(IC1-IO35-Pad28)") (class "Default")
      (node (ref "IC1") (pin "28") (pinfunction "IO35_28") (pintype "passive"))
    )
    (net (code "64") (name "unconnected-(IC1-IO36-Pad29)") (class "Default")
      (node (ref "IC1") (pin "29") (pinfunction "IO36_29") (pintype "passive"))
    )
    (net (code "65") (name "unconnected-(IC1-IO37-Pad30)") (class "Default")
      (node (ref "IC1") (pin "30") (pinfunction "IO37_30") (pintype "passive"))
    )
    (net (code "66") (name "unconnected-(IC1-IO38-Pad31)") (class "Default")
      (node (ref "IC1") (pin "31") (pinfunction "IO38_31") (pintype "passive"))
    )
    (net (code "67") (name "unconnected-(IC1-IO39-Pad32)") (class "Default")
      (node (ref "IC1") (pin "32") (pinfunction "IO39_32") (pintype "passive"))
    )
    (net (code "68") (name "unconnected-(IC1-IO40-Pad33)") (class "Default")
      (node (ref "IC1") (pin "33") (pinfunction "IO40_33") (pintype "passive"))
    )
    (net (code "69") (name "unconnected-(IC1-IO41-Pad34)") (class "Default")
      (node (ref "IC1") (pin "34") (pinfunction "IO41_34") (pintype "passive"))
    )
    (net (code "70") (name "unconnected-(IC1-IO42-Pad35)") (class "Default")
      (node (ref "IC1") (pin "35") (pinfunction "IO42_35") (pintype "passive"))
    )
    (net (code "71") (name "unconnected-(IC1-IO45-Pad26)") (class "Default")
      (node (ref "IC1") (pin "26") (pinfunction "IO45_26") (pintype "passive"))
    )
    (net (code "72") (name "unconnected-(IC1-IO47-Pad24)") (class "Default")
      (node (ref "IC1") (pin "24") (pinfunction "IO47_24") (pintype "passive"))
    )
    (net (code "73") (name "unconnected-(IC1-IO48-Pad25)") (class "Default")
      (node (ref "IC1") (pin "25") (pinfunction "IO48_25") (pintype "passive"))
    )
    (net (code "74") (name "unconnected-(IC2-CHR0-Pad15)") (class "Default")
      (node (ref "IC2") (pin "15") (pinfunction "CHR0_15") (pintype "output"))
    )
    (net (code "75") (name "unconnected-(IC2-CHR1-Pad14)") (class "Default")
      (node (ref "IC2") (pin "14") (pinfunction "CHR1_14") (pintype "output"))
    )
    (net (code "76") (name "unconnected-(IC2-CHREN-Pad13)") (class "Default")
      (node (ref "IC2") (pin "13") (pinfunction "CHREN_13") (pintype "output"))
    )
    (net (code "77") (name "unconnected-(IC2-CTS-Pad23)") (class "Default")
      (node (ref "IC2") (pin "23") (pinfunction "CTS_23") (pintype "input"))
    )
    (net (code "78") (name "unconnected-(IC2-DCD-Pad1)") (class "Default")
      (node (ref "IC2") (pin "1") (pinfunction "DCD_1") (pintype "input"))
    )
    (net (code "79") (name "unconnected-(IC2-DSR-Pad27)") (class "Default")
      (node (ref "IC2") (pin "27") (pinfunction "DSR_27") (pintype "input"))
    )
    (net (code "80") (name "unconnected-(IC2-GPIO.0{slash}TXT-Pad19)") (class "Default")
      (node (ref "IC2") (pin "19") (pinfunction "GPIO.0/TXT_19") (pintype "bidirectional"))
    )
    (net (code "81") (name "unconnected-(IC2-GPIO.1{slash}RXT-Pad18)") (class "Default")
      (node (ref "IC2") (pin "18") (pinfunction "GPIO.1/RXT_18") (pintype "bidirectional"))
    )
    (net (code "82") (name "unconnected-(IC2-GPIO.2{slash}RS485-Pad17)") (class "Default")
      (node (ref "IC2") (pin "17") (pinfunction "GPIO.2/RS485_17") (pintype "bidirectional"))
    )
    (net (code "83") (name "unconnected-(IC2-GPIO.3{slash}WAKEUP-Pad16)") (class "Default")
      (node (ref "IC2") (pin "16") (pinfunction "GPIO.3/WAKEUP_16") (pintype "bidirectional"))
    )
    (net (code "84") (name "unconnected-(IC2-GPIO.4-Pad22)") (class "Default")
      (node (ref "IC2") (pin "22") (pinfunction "GPIO.4_22") (pintype "bidirectional"))
    )
    (net (code "85") (name "unconnected-(IC2-GPIO.5-Pad21)") (class "Default")
      (node (ref "IC2") (pin "21") (pinfunction "GPIO.5_21") (pintype "bidirectional"))
    )
    (net (code "86") (name "unconnected-(IC2-GPIO.6-Pad20)") (class "Default")
      (node (ref "IC2") (pin "20") (pinfunction "GPIO.6_20") (pintype "bidirectional"))
    )
    (net (code "87") (name "unconnected-(IC2-NC-Pad10)") (class "Default")
      (node (ref "IC2") (pin "10") (pinfunction "NC_10") (pintype "passive"))
    )
    (net (code "88") (name "unconnected-(IC2-RI{slash}CLK-Pad2)") (class "Default")
      (node (ref "IC2") (pin "2") (pinfunction "RI/CLK_2") (pintype "bidirectional"))
    )
    (net (code "89") (name "unconnected-(IC2-SUSPEND-Pad12)") (class "Default")
      (node (ref "IC2") (pin "12") (pinfunction "SUSPEND_12") (pintype "output"))
    )
    (net (code "90") (name "unconnected-(IC4-NC-Pad6)") (class "Default")
      (node (ref "IC4") (pin "6") (pinfunction "NC_6") (pintype "passive"))
    )
    (net (code "91") (name "unconnected-(IC5-INTN_1-Pad12)") (class "Default")
      (node (ref "IC5") (pin "12") (pinfunction "INTN_1_12") (pintype "passive"))
    )
    (net (code "92") (name "unconnected-(IC5-INTN_2-Pad11)") (class "Default")
      (node (ref "IC5") (pin "11") (pinfunction "INTN_2_11") (pintype "passive"))
    )
    (net (code "93") (name "unconnected-(IC5-NC_1-Pad5)") (class "Default")
      (node (ref "IC5") (pin "5") (pinfunction "NC_1_5") (pintype "passive"))
    )
    (net (code "94") (name "unconnected-(IC5-NC_2-Pad8)") (class "Default")
      (node (ref "IC5") (pin "8") (pinfunction "NC_2_8") (pintype "passive"))
    )
    (net (code "95") (name "unconnected-(IC5-NC_3-Pad10)") (class "Default")
      (node (ref "IC5") (pin "10") (pinfunction "NC_3_10") (pintype "passive"))
    )
    (net (code "96") (name "unconnected-(J1-ID-Pad4)") (class "Default")
      (node (ref "J1") (pin "4") (pinfunction "ID_4") (pintype "passive"))
    )
    (net (code "97") (name "unconnected-(S1-Pad3)") (class "Default")
      (node (ref "S1") (pin "3") (pinfunction "3_3") (pintype "passive"))
    )
  )
)
